# ESP32_with_USBC.net
KiCad netlist of a schematic drawn in Altium Designer
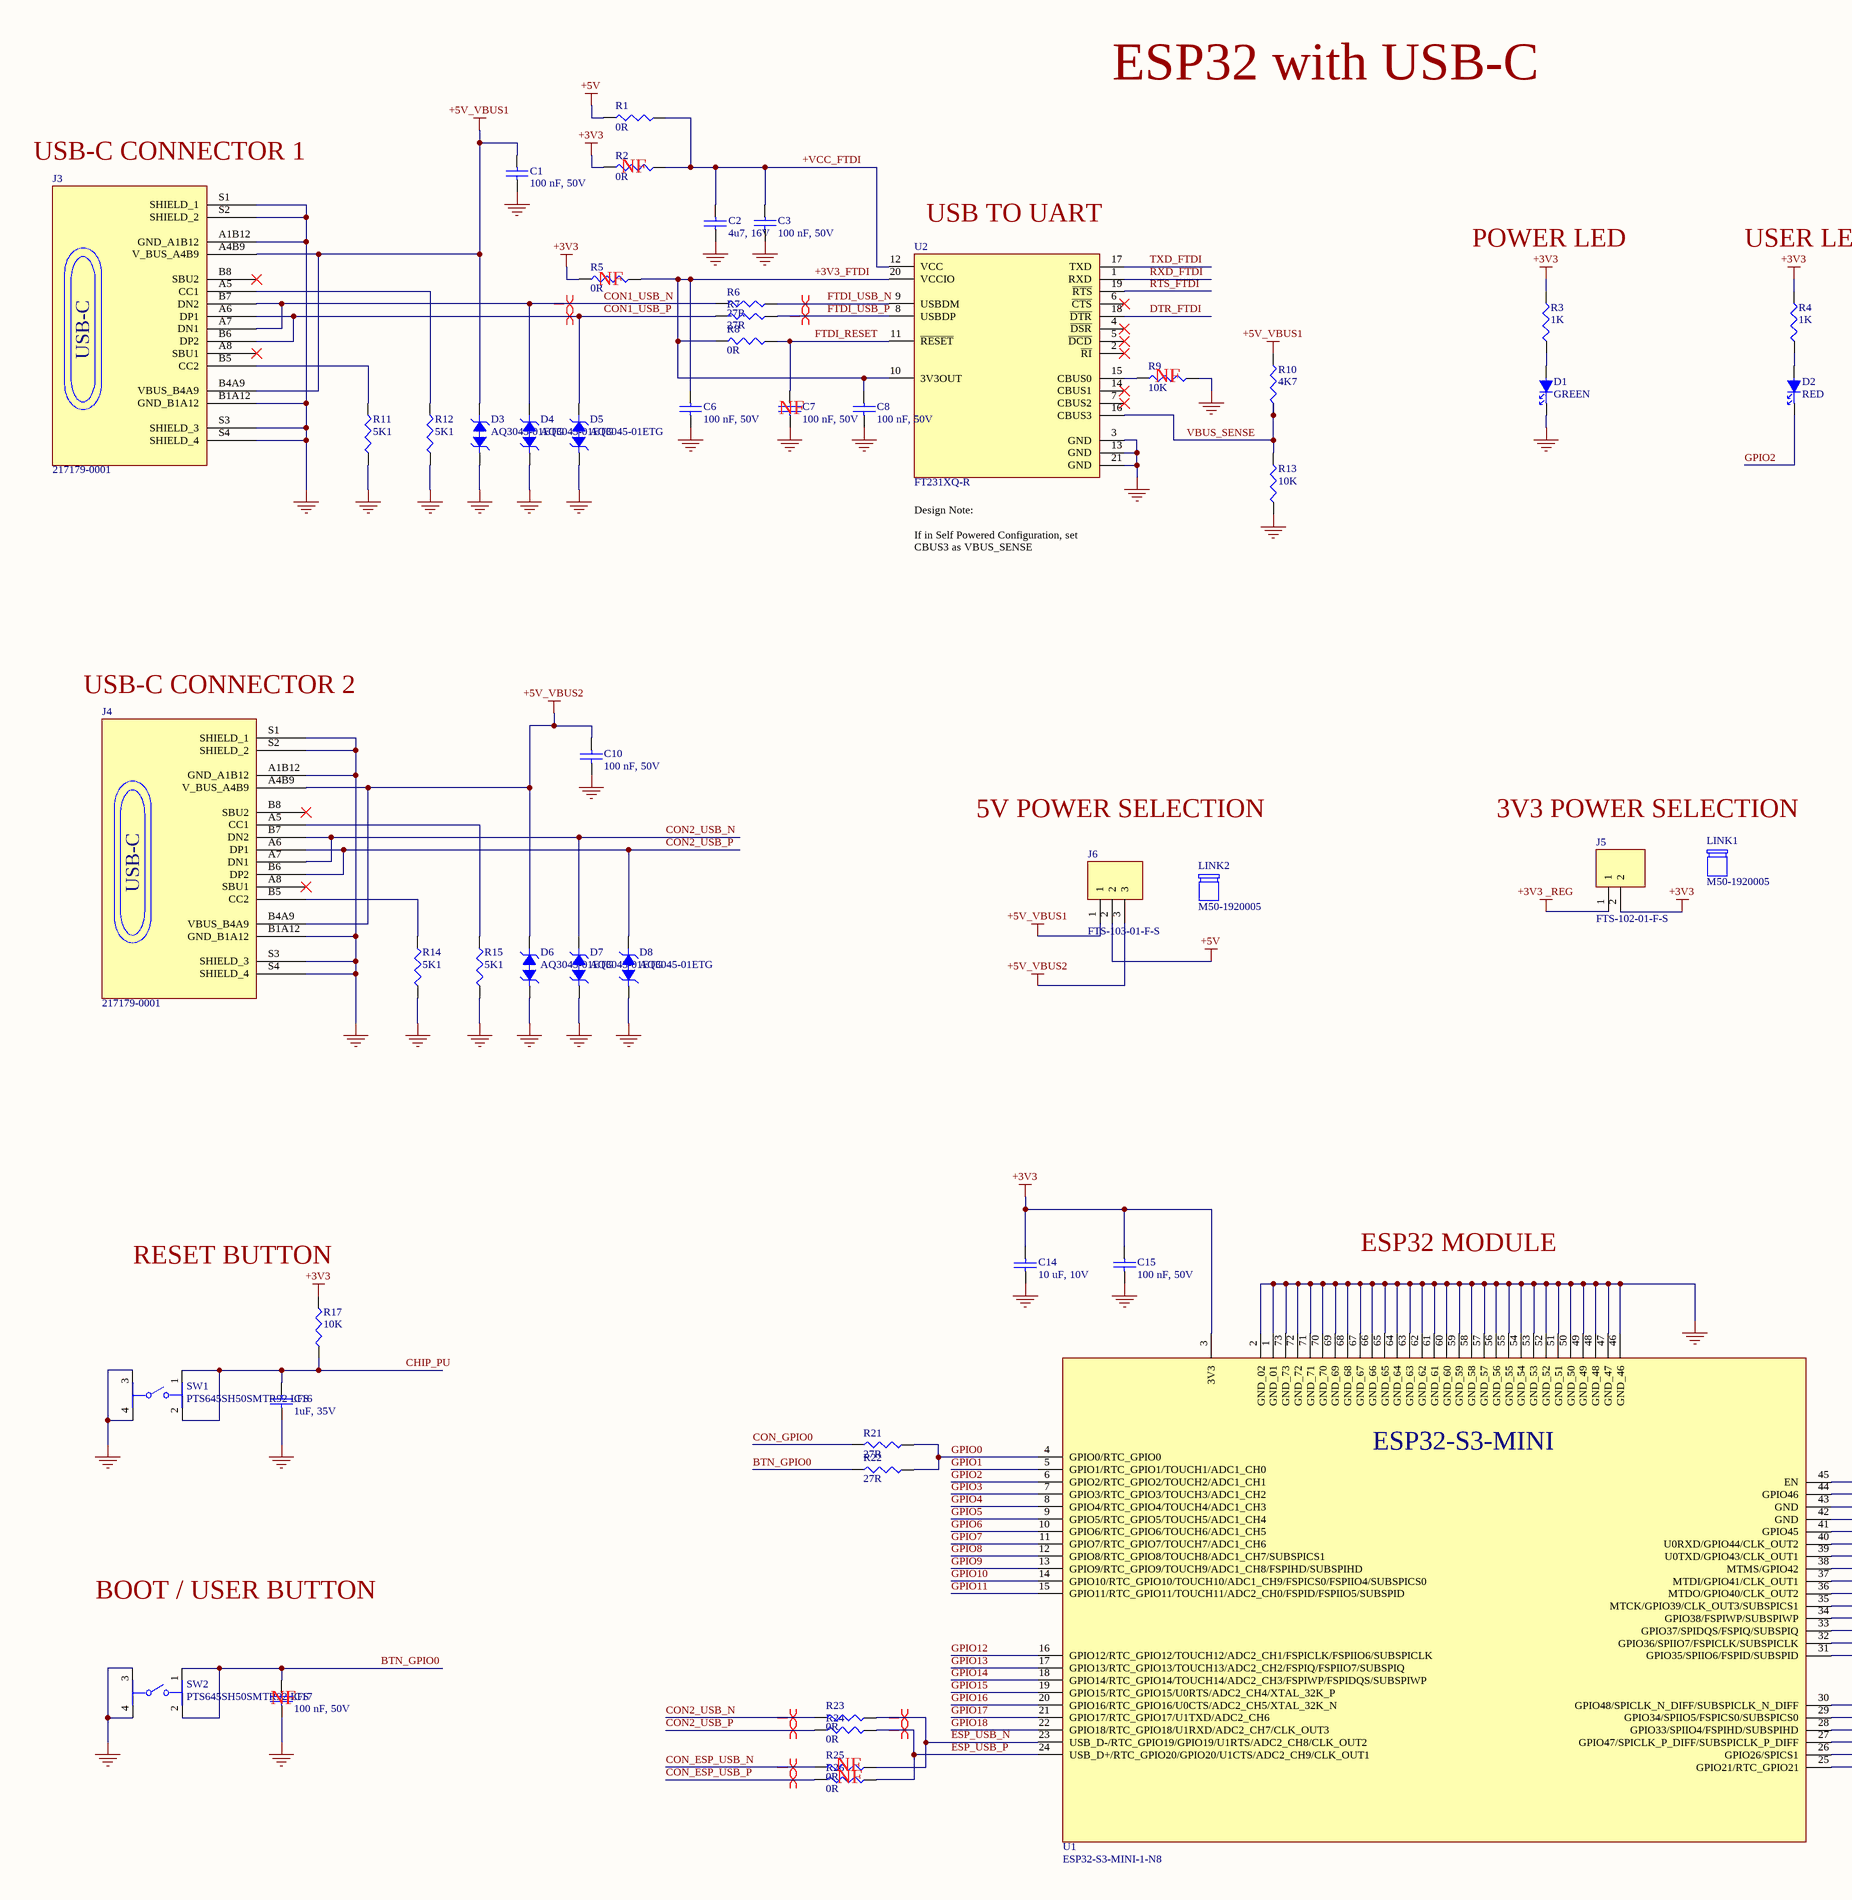
[diagram p0: ESP32 with USBC.SchDoc, left]
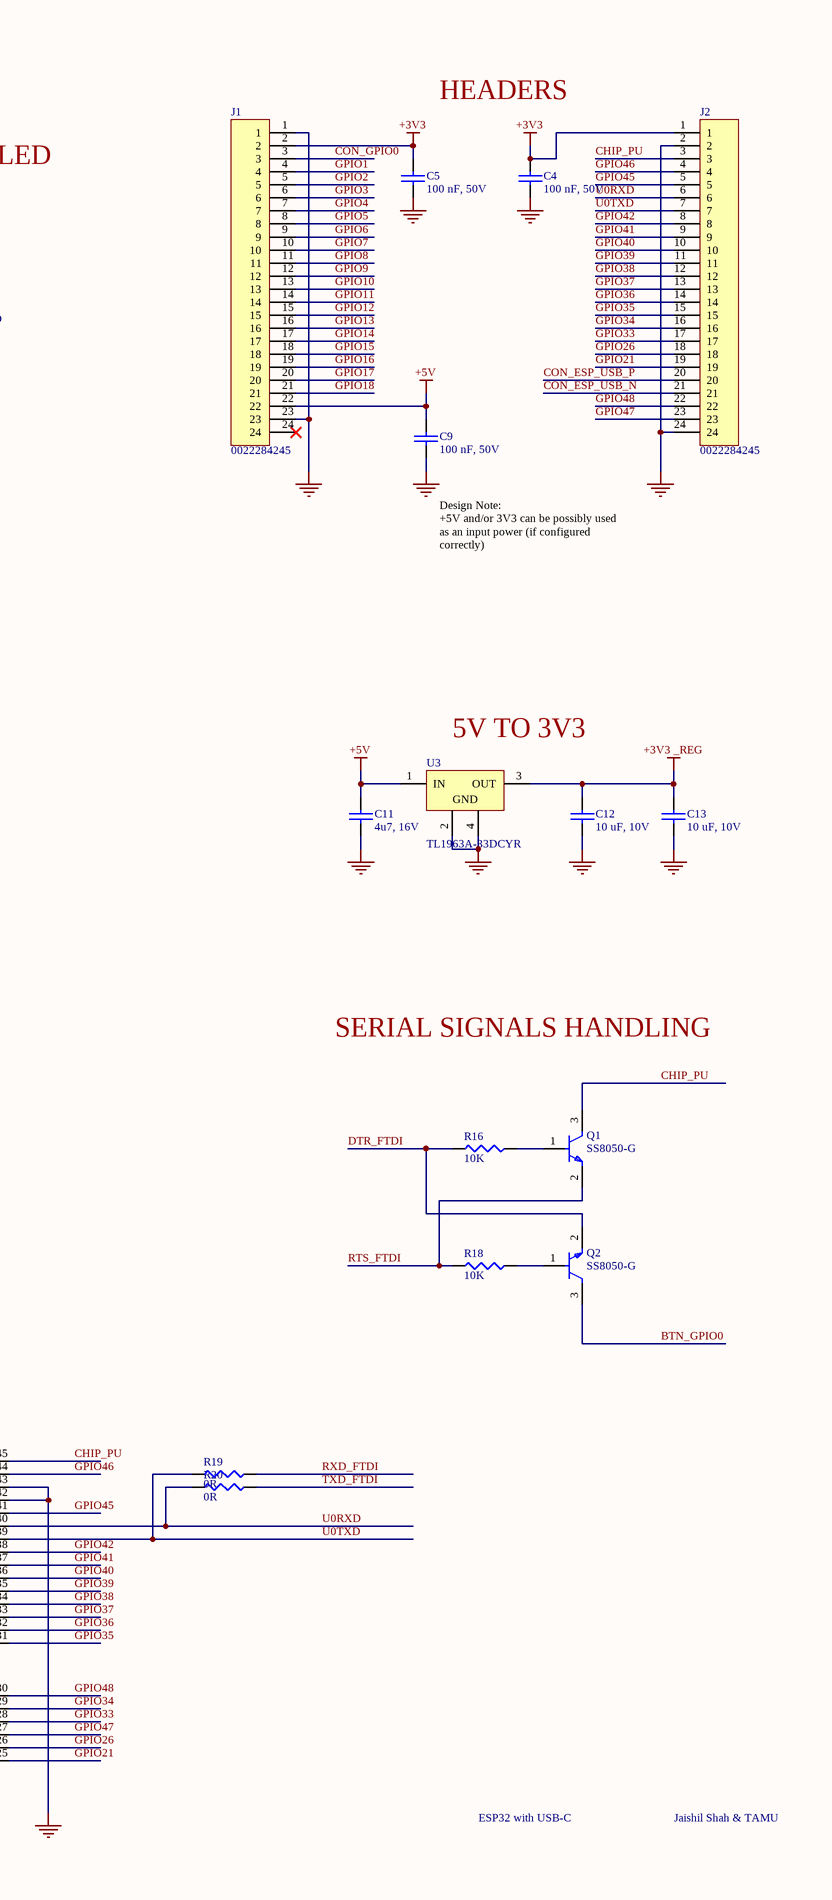
[diagram p1: ESP32 with USBC.SchDoc, right]

(export (version "E")
  (design (tool "Eeschema 10.0.6"))
  (components
    (comp (ref "C1")
      (value "100 nF, 50V")
      (footprint "CAPC1005X55N")
      (description "CAP CER 0.1UF 50V X7R 0402")
      (fields
        (field (name "MANUFACTURER") "Samsung")
        (field (name "MANUFACTURER PART NUMBER") "CL05B104KB54PNC")
      )
      (libsource (lib "Schlib") (part "CL05B104KB54PNC"))
    )
    (comp (ref "C2")
      (value "4u7, 16V")
      (footprint "CAPC1005X55N")
      (description "CAP CER 4.7UF 16V X5R 0402")
      (fields
        (field (name "MANUFACTURER") "Samsung")
        (field (name "MANUFACTURER PART NUMBER") "CL05A475MO5NUNC")
      )
      (libsource (lib "Schlib") (part "CL05A475MO5NUNC"))
    )
    (comp (ref "C3")
      (value "100 nF, 50V")
      (footprint "CAPC1005X55N")
      (description "CAP CER 0.1UF 50V X7R 0402")
      (fields
        (field (name "MANUFACTURER") "Samsung")
        (field (name "MANUFACTURER PART NUMBER") "CL05B104KB54PNC")
      )
      (libsource (lib "Schlib") (part "CL05B104KB54PNC"))
    )
    (comp (ref "C4")
      (value "100 nF, 50V")
      (footprint "CAPC1005X55N")
      (description "CAP CER 0.1UF 50V X7R 0402")
      (fields
        (field (name "MANUFACTURER") "Samsung")
        (field (name "MANUFACTURER PART NUMBER") "CL05B104KB54PNC")
      )
      (libsource (lib "Schlib") (part "CL05B104KB54PNC"))
    )
    (comp (ref "C5")
      (value "100 nF, 50V")
      (footprint "CAPC1005X55N")
      (description "CAP CER 0.1UF 50V X7R 0402")
      (fields
        (field (name "MANUFACTURER") "Samsung")
        (field (name "MANUFACTURER PART NUMBER") "CL05B104KB54PNC")
      )
      (libsource (lib "Schlib") (part "CL05B104KB54PNC"))
    )
    (comp (ref "C6")
      (value "100 nF, 50V")
      (footprint "CAPC1005X55N")
      (description "CAP CER 0.1UF 50V X7R 0402")
      (fields
        (field (name "MANUFACTURER") "Samsung")
        (field (name "MANUFACTURER PART NUMBER") "CL05B104KB54PNC")
      )
      (libsource (lib "Schlib") (part "CL05B104KB54PNC"))
    )
    (comp (ref "C7")
      (value "100 nF, 50V")
      (footprint "CAPC1005X55N")
      (description "CAP CER 0.1UF 50V X7R 0402")
      (fields
        (field (name "MANUFACTURER") "Samsung")
        (field (name "MANUFACTURER PART NUMBER") "CL05B104KB54PNC")
      )
      (libsource (lib "Schlib") (part "CL05B104KB54PNC"))
    )
    (comp (ref "C8")
      (value "100 nF, 50V")
      (footprint "CAPC1005X55N")
      (description "CAP CER 0.1UF 50V X7R 0402")
      (fields
        (field (name "MANUFACTURER") "Samsung")
        (field (name "MANUFACTURER PART NUMBER") "CL05B104KB54PNC")
      )
      (libsource (lib "Schlib") (part "CL05B104KB54PNC"))
    )
    (comp (ref "C9")
      (value "100 nF, 50V")
      (footprint "CAPC1005X55N")
      (description "CAP CER 0.1UF 50V X7R 0402")
      (fields
        (field (name "MANUFACTURER") "Samsung")
        (field (name "MANUFACTURER PART NUMBER") "CL05B104KB54PNC")
      )
      (libsource (lib "Schlib") (part "CL05B104KB54PNC"))
    )
    (comp (ref "C10")
      (value "100 nF, 50V")
      (footprint "CAPC1005X55N")
      (description "CAP CER 0.1UF 50V X7R 0402")
      (fields
        (field (name "MANUFACTURER") "Samsung")
        (field (name "MANUFACTURER PART NUMBER") "CL05B104KB54PNC")
      )
      (libsource (lib "Schlib") (part "CL05B104KB54PNC"))
    )
    (comp (ref "C11")
      (value "4u7, 16V")
      (footprint "CAPC1005X55N")
      (description "CAP CER 4.7UF 16V X5R 0402")
      (fields
        (field (name "MANUFACTURER") "Samsung")
        (field (name "MANUFACTURER PART NUMBER") "CL05A475MO5NUNC")
      )
      (libsource (lib "Schlib") (part "CL05A475MO5NUNC"))
    )
    (comp (ref "C12")
      (value "10 uF, 10V")
      (footprint "CAPC1005X55N")
      (description "CAP CER 10UF 10V X5R 0402")
      (fields
        (field (name "MANUFACTURER") "Samsung")
        (field (name "MANUFACTURER PART NUMBER") "CL05A106MP8NUB8")
      )
      (libsource (lib "Schlib") (part "CL05A106MP8NUB8"))
    )
    (comp (ref "C13")
      (value "10 uF, 10V")
      (footprint "CAPC1005X55N")
      (description "CAP CER 10UF 10V X5R 0402")
      (fields
        (field (name "MANUFACTURER") "Samsung")
        (field (name "MANUFACTURER PART NUMBER") "CL05A106MP8NUB8")
      )
      (libsource (lib "Schlib") (part "CL05A106MP8NUB8"))
    )
    (comp (ref "C14")
      (value "10 uF, 10V")
      (footprint "CAPC1005X55N")
      (description "CAP CER 10UF 10V X5R 0402")
      (fields
        (field (name "MANUFACTURER") "Samsung")
        (field (name "MANUFACTURER PART NUMBER") "CL05A106MP8NUB8")
      )
      (libsource (lib "Schlib") (part "CL05A106MP8NUB8"))
    )
    (comp (ref "C15")
      (value "100 nF, 50V")
      (footprint "CAPC1005X55N")
      (description "CAP CER 0.1UF 50V X7R 0402")
      (fields
        (field (name "MANUFACTURER") "Samsung")
        (field (name "MANUFACTURER PART NUMBER") "CL05B104KB54PNC")
      )
      (libsource (lib "Schlib") (part "CL05B104KB54PNC"))
    )
    (comp (ref "C16")
      (value "1uF, 35V")
      (footprint "CAPC1005X55N")
      (description "CAP CER 1UF 35V X5R 0402")
      (fields
        (field (name "MANUFACTURER") "Samsung")
        (field (name "MANUFACTURER PART NUMBER") "CL05A105KL5NRNC")
      )
      (libsource (lib "Schlib") (part "CL05A105KL5NRNC"))
    )
    (comp (ref "C17")
      (value "100 nF, 50V")
      (footprint "CAPC1005X55N")
      (description "CAP CER 0.1UF 50V X7R 0402")
      (fields
        (field (name "MANUFACTURER") "Samsung")
        (field (name "MANUFACTURER PART NUMBER") "CL05B104KB54PNC")
      )
      (libsource (lib "Schlib") (part "CL05B104KB54PNC"))
    )
    (comp (ref "D1")
      (value "GREEN")
      (footprint "LED0402G")
      (description "LED GREEN DIFFUSED 0402 SMD")
      (fields
        (field (name "MANUFACTURER") "Vishay")
        (field (name "MANUFACTURER PART NUMBER") "VLMTG1500-GS08")
      )
      (libsource (lib "Schlib") (part "VLMTG1500-GS08"))
    )
    (comp (ref "D2")
      (value "RED")
      (footprint "LED0402R")
      (description "LED RED 0402 SMD")
      (fields
        (field (name "MANUFACTURER") "Vishay")
        (field (name "MANUFACTURER PART NUMBER") "VLMS1500-GS08")
      )
      (libsource (lib "Schlib") (part "VLMS1500-GS08"))
    )
    (comp (ref "D3")
      (value "AQ3045-01ETG")
      (footprint "SOD882")
      (description "TVS DIODE 5.3VWM 12VC SOD882")
      (fields (field (name "MANUFACTURER") "Littelfuse"))
      (libsource (lib "Schlib") (part "AQ3045-01ETG"))
    )
    (comp (ref "D4")
      (value "AQ3045-01ETG")
      (footprint "SOD882")
      (description "TVS DIODE 5.3VWM 12VC SOD882")
      (fields (field (name "MANUFACTURER") "Littelfuse"))
      (libsource (lib "Schlib") (part "AQ3045-01ETG"))
    )
    (comp (ref "D5")
      (value "AQ3045-01ETG")
      (footprint "SOD882")
      (description "TVS DIODE 5.3VWM 12VC SOD882")
      (fields (field (name "MANUFACTURER") "Littelfuse"))
      (libsource (lib "Schlib") (part "AQ3045-01ETG"))
    )
    (comp (ref "D6")
      (value "AQ3045-01ETG")
      (footprint "SOD882")
      (description "TVS DIODE 5.3VWM 12VC SOD882")
      (fields (field (name "MANUFACTURER") "Littelfuse"))
      (libsource (lib "Schlib") (part "AQ3045-01ETG"))
    )
    (comp (ref "D7")
      (value "AQ3045-01ETG")
      (footprint "SOD882")
      (description "TVS DIODE 5.3VWM 12VC SOD882")
      (fields (field (name "MANUFACTURER") "Littelfuse"))
      (libsource (lib "Schlib") (part "AQ3045-01ETG"))
    )
    (comp (ref "D8")
      (value "AQ3045-01ETG")
      (footprint "SOD882")
      (description "TVS DIODE 5.3VWM 12VC SOD882")
      (fields (field (name "MANUFACTURER") "Littelfuse") (field (name "LCSC PART NUMBER") "C3710326"))
      (libsource (lib "Schlib") (part "AQ3045-01ETG"))
    )
    (comp (ref "J1")
      (value "0022284245")
      (footprint "HDR_1X24_2.54MM")
      (description "CONN HEADER VERT 24POS 2.54MM")
      (fields (field (name "MANUFACTURER") "Molex") (field (name "LCSC PART NUMBER") "C7145888"))
      (libsource (lib "") (part "0022284245_1"))
    )
    (comp (ref "J2")
      (value "0022284245")
      (footprint "HDR_1X24_2.54MM")
      (description "CONN HEADER VERT 24POS 2.54MM")
      (fields (field (name "MANUFACTURER") "Molex") (field (name "LCSC PART NUMBER") "C7145888"))
      (libsource (lib "Schlib") (part "0022284245"))
    )
    (comp (ref "J3")
      (value "217179-0001")
      (footprint "FP-2171790001-MFG")
      (description "CONN RCP USB2.0 TYP C 24P SMD RA")
      (fields (field (name "MANUFACTURER") "Molex") (field (name "LCSC PART NUMBER") "C3197684"))
      (libsource (lib "Schlib") (part "217179-0001"))
    )
    (comp (ref "J4")
      (value "217179-0001")
      (footprint "FP-2171790001-MFG")
      (description "CONN RCP USB2.0 TYP C 24P SMD RA")
      (fields (field (name "MANUFACTURER") "Molex") (field (name "LCSC PART NUMBER") "C3197684"))
      (libsource (lib "Schlib") (part "217179-0001"))
    )
    (comp (ref "J5")
      (value "FTS-102-01-F-S")
      (footprint "HDR_1X2_1.27MM")
      (description "CONN HEADER VERT 2POS 1.27MM")
      (fields (field (name "MANUFACTURER") "Samtec") (field (name "LCSC PART NUMBER") "C6045317"))
      (libsource (lib "Schlib") (part "FTS-102-01-F-S"))
    )
    (comp (ref "J6")
      (value "FTS-103-01-F-S")
      (footprint "HDR_1X3_1.27MM")
      (description "CONN HEADER VERT 3POS 1.27MM")
      (fields (field (name "MANUFACTURER") "Samtec") (field (name "LCSC PART NUMBER") "C3333578"))
      (libsource (lib "Schlib") (part "FTS-103-01-F-S"))
    )
    (comp (ref "LINK1")
      (value "M50-1920005")
      (description "CONN SHUNT 1.27MM RED")
      (fields (field (name "MANUFACTURER") "Harwin") (field (name "LCSC PART NUMBER") "C6985646"))
      (libsource (lib "Schlib") (part "M50-1920005"))
    )
    (comp (ref "LINK2")
      (value "M50-1920005")
      (description "CONN SHUNT 1.27MM RED")
      (fields (field (name "MANUFACTURER") "Harwin") (field (name "LCSC PART NUMBER") "C6985646"))
      (libsource (lib "Schlib") (part "M50-1920005"))
    )
    (comp (ref "Q1")
      (value "SS8050-G")
      (footprint "FP-SS8050-G-IPC_B")
      (description "TRANS NPN 25V 1.5A SOT23-3")
      (fields (field (name "MANUFACTURER") "Comchip") (field (name "LCSC PART NUMBER") "C164885"))
      (libsource (lib "Schlib") (part "SS8050-G"))
    )
    (comp (ref "Q2")
      (value "SS8050-G")
      (footprint "FP-SS8050-G-IPC_B")
      (description "TRANS NPN 25V 1.5A SOT23-3")
      (fields (field (name "MANUFACTURER") "Comchip") (field (name "LCSC PART NUMBER") "C164885"))
      (libsource (lib "Schlib") (part "SS8050-G"))
    )
    (comp (ref "R1")
      (value "0R")
      (footprint "RESC1005X37N")
      (description "RES 0 OHM JUMPER 1/16W 0402")
      (fields
        (field (name "MANUFACTURER") "Yageo")
        (field (name "MANUFACTURER PART NUMBER") "RC0402JR-070RL")
      )
      (libsource (lib "Schlib") (part "RC0402JR-070RL"))
    )
    (comp (ref "R2")
      (value "0R")
      (footprint "RESC1005X37N")
      (description "RES 0 OHM JUMPER 1/16W 0402")
      (fields
        (field (name "MANUFACTURER") "Yageo")
        (field (name "MANUFACTURER PART NUMBER") "RC0402JR-070RL")
      )
      (libsource (lib "Schlib") (part "RC0402JR-070RL"))
    )
    (comp (ref "R3")
      (value "1K")
      (footprint "RESC1005X37N")
      (description "RES 1K OHM 1% 1/16W 0402")
      (fields
        (field (name "MANUFACTURER") "Yageo")
        (field (name "MANUFACTURER PART NUMBER") "RC0402FR-071KL")
      )
      (libsource (lib "Schlib") (part "RC0402FR-071KL"))
    )
    (comp (ref "R4")
      (value "1K")
      (footprint "RESC1005X37N")
      (description "RES 1K OHM 1% 1/16W 0402")
      (fields
        (field (name "MANUFACTURER") "Yageo")
        (field (name "MANUFACTURER PART NUMBER") "RC0402FR-071KL")
      )
      (libsource (lib "Schlib") (part "RC0402FR-071KL"))
    )
    (comp (ref "R5")
      (value "0R")
      (footprint "RESC1005X37N")
      (description "RES 0 OHM JUMPER 1/16W 0402")
      (fields
        (field (name "MANUFACTURER") "Yageo")
        (field (name "MANUFACTURER PART NUMBER") "RC0402JR-070RL")
      )
      (libsource (lib "Schlib") (part "RC0402JR-070RL"))
    )
    (comp (ref "R6")
      (value "27R")
      (footprint "RESC1005X37N")
      (description "RES 27 OHM 1% 1/16W 0402")
      (fields
        (field (name "MANUFACTURER") "Yageo")
        (field (name "MANUFACTURER PART NUMBER") "RC0402FR-0727RL")
      )
      (libsource (lib "Schlib") (part "RC0402FR-0727RL"))
    )
    (comp (ref "R7")
      (value "27R")
      (footprint "RESC1005X37N")
      (description "RES 27 OHM 1% 1/16W 0402")
      (fields
        (field (name "MANUFACTURER") "Yageo")
        (field (name "MANUFACTURER PART NUMBER") "RC0402FR-0727RL")
      )
      (libsource (lib "Schlib") (part "RC0402FR-0727RL"))
    )
    (comp (ref "R8")
      (value "0R")
      (footprint "RESC1005X37N")
      (description "RES 0 OHM JUMPER 1/16W 0402")
      (fields
        (field (name "MANUFACTURER") "Yageo")
        (field (name "MANUFACTURER PART NUMBER") "RC0402JR-070RL")
      )
      (libsource (lib "Schlib") (part "RC0402JR-070RL"))
    )
    (comp (ref "R9")
      (value "10K")
      (footprint "RESC1005X37N")
      (description "RES SMD 10K OHM 1% 1/16W 0402")
      (fields
        (field (name "MANUFACTURER") "Yageo")
        (field (name "MANUFACTURER PART NUMBER") "AC0402FR-0710KL")
      )
      (libsource (lib "Schlib") (part "AC0402FR-0710KL"))
    )
    (comp (ref "R10")
      (value "4K7")
      (footprint "RESC1005X37N")
      (description "RES 4.7K OHM 1% 1/16W 0402")
      (fields
        (field (name "MANUFACTURER") "Yageo")
        (field (name "MANUFACTURER PART NUMBER") "RC0402FR-074K7L")
      )
      (libsource (lib "Schlib") (part "RC0402FR-074K7L"))
    )
    (comp (ref "R11")
      (value "5K1")
      (footprint "RESC1005X37N")
      (description "RES SMD 5.1K OHM 1% 1/16W 0402")
      (fields
        (field (name "MANUFACTURER") "Yageo")
        (field (name "MANUFACTURER PART NUMBER") "AC0402FR-075K1L")
      )
      (libsource (lib "Schlib") (part "AC0402FR-075K1L"))
    )
    (comp (ref "R12")
      (value "5K1")
      (footprint "RESC1005X37N")
      (description "RES SMD 5.1K OHM 1% 1/16W 0402")
      (fields
        (field (name "MANUFACTURER") "Yageo")
        (field (name "MANUFACTURER PART NUMBER") "AC0402FR-075K1L")
      )
      (libsource (lib "Schlib") (part "AC0402FR-075K1L"))
    )
    (comp (ref "R13")
      (value "10K")
      (footprint "RESC1005X37N")
      (description "RES SMD 10K OHM 1% 1/16W 0402")
      (fields
        (field (name "MANUFACTURER") "Yageo")
        (field (name "MANUFACTURER PART NUMBER") "AC0402FR-0710KL")
      )
      (libsource (lib "Schlib") (part "AC0402FR-0710KL"))
    )
    (comp (ref "R14")
      (value "5K1")
      (footprint "RESC1005X37N")
      (description "RES SMD 5.1K OHM 1% 1/16W 0402")
      (fields
        (field (name "MANUFACTURER") "Yageo")
        (field (name "MANUFACTURER PART NUMBER") "AC0402FR-075K1L")
      )
      (libsource (lib "Schlib") (part "AC0402FR-075K1L"))
    )
    (comp (ref "R15")
      (value "5K1")
      (footprint "RESC1005X37N")
      (description "RES SMD 5.1K OHM 1% 1/16W 0402")
      (fields
        (field (name "MANUFACTURER") "Yageo")
        (field (name "MANUFACTURER PART NUMBER") "AC0402FR-075K1L")
      )
      (libsource (lib "Schlib") (part "AC0402FR-075K1L"))
    )
    (comp (ref "R16")
      (value "10K")
      (footprint "RESC1005X37N")
      (description "RES SMD 10K OHM 1% 1/16W 0402")
      (fields
        (field (name "MANUFACTURER") "Yageo")
        (field (name "MANUFACTURER PART NUMBER") "AC0402FR-0710KL")
      )
      (libsource (lib "Schlib") (part "AC0402FR-0710KL"))
    )
    (comp (ref "R17")
      (value "10K")
      (footprint "RESC1005X37N")
      (description "RES SMD 10K OHM 1% 1/16W 0402")
      (fields
        (field (name "MANUFACTURER") "Yageo")
        (field (name "MANUFACTURER PART NUMBER") "AC0402FR-0710KL")
      )
      (libsource (lib "Schlib") (part "AC0402FR-0710KL"))
    )
    (comp (ref "R18")
      (value "10K")
      (footprint "RESC1005X37N")
      (description "RES SMD 10K OHM 1% 1/16W 0402")
      (fields
        (field (name "MANUFACTURER") "Yageo")
        (field (name "MANUFACTURER PART NUMBER") "AC0402FR-0710KL")
      )
      (libsource (lib "Schlib") (part "AC0402FR-0710KL"))
    )
    (comp (ref "R19")
      (value "0R")
      (footprint "RESC1005X37N")
      (description "RES 0 OHM JUMPER 1/16W 0402")
      (fields
        (field (name "MANUFACTURER") "Yageo")
        (field (name "MANUFACTURER PART NUMBER") "RC0402JR-070RL")
      )
      (libsource (lib "Schlib") (part "RC0402JR-070RL"))
    )
    (comp (ref "R20")
      (value "0R")
      (footprint "RESC1005X37N")
      (description "RES 0 OHM JUMPER 1/16W 0402")
      (fields
        (field (name "MANUFACTURER") "Yageo")
        (field (name "MANUFACTURER PART NUMBER") "RC0402JR-070RL")
      )
      (libsource (lib "Schlib") (part "RC0402JR-070RL"))
    )
    (comp (ref "R21")
      (value "27R")
      (footprint "RESC1005X37N")
      (description "RES 27 OHM 1% 1/16W 0402")
      (fields
        (field (name "MANUFACTURER") "Yageo")
        (field (name "MANUFACTURER PART NUMBER") "RC0402FR-0727RL")
      )
      (libsource (lib "Schlib") (part "RC0402FR-0727RL"))
    )
    (comp (ref "R22")
      (value "27R")
      (footprint "RESC1005X37N")
      (description "RES 27 OHM 1% 1/16W 0402")
      (fields
        (field (name "MANUFACTURER") "Yageo")
        (field (name "MANUFACTURER PART NUMBER") "RC0402FR-0727RL")
      )
      (libsource (lib "Schlib") (part "RC0402FR-0727RL"))
    )
    (comp (ref "R23")
      (value "0R")
      (footprint "RESC1005X37N")
      (description "RES 0 OHM JUMPER 1/16W 0402")
      (fields
        (field (name "MANUFACTURER") "Yageo")
        (field (name "MANUFACTURER PART NUMBER") "RC0402JR-070RL")
      )
      (libsource (lib "Schlib") (part "RC0402JR-070RL"))
    )
    (comp (ref "R24")
      (value "0R")
      (footprint "RESC1005X37N")
      (description "RES 0 OHM JUMPER 1/16W 0402")
      (fields
        (field (name "MANUFACTURER") "Yageo")
        (field (name "MANUFACTURER PART NUMBER") "RC0402JR-070RL")
      )
      (libsource (lib "Schlib") (part "RC0402JR-070RL"))
    )
    (comp (ref "R25")
      (value "0R")
      (footprint "RESC1005X37N")
      (description "RES 0 OHM JUMPER 1/16W 0402")
      (fields
        (field (name "MANUFACTURER") "Yageo")
        (field (name "MANUFACTURER PART NUMBER") "RC0402JR-070RL")
      )
      (libsource (lib "Schlib") (part "RC0402JR-070RL"))
    )
    (comp (ref "R26")
      (value "0R")
      (footprint "RESC1005X37N")
      (description "RES 0 OHM JUMPER 1/16W 0402")
      (fields
        (field (name "MANUFACTURER") "Yageo")
        (field (name "MANUFACTURER PART NUMBER") "RC0402JR-070RL")
      )
      (libsource (lib "Schlib") (part "RC0402JR-070RL"))
    )
    (comp (ref "SW1")
      (value "PTS645SH50SMTR92 LFS")
      (footprint "FP-PTS645SH50SMTR92LFS-MFG")
      (description "SWITCH TACTILE SPST-NO 0.05A 12V")
      (fields
        (field (name "MANUFACTURER") "ITT C&K")
        (field (name "MANUFACTURER PART NUMBER") "PTS645SH50SMTR92LFS")
      )
      (libsource (lib "Schlib") (part "PTS645SH50SMTR92LFS"))
    )
    (comp (ref "SW2")
      (value "PTS645SH50SMTR92 LFS")
      (footprint "FP-PTS645SH50SMTR92LFS-MFG")
      (description "SWITCH TACTILE SPST-NO 0.05A 12V")
      (fields
        (field (name "MANUFACTURER") "ITT C&K")
        (field (name "MANUFACTURER PART NUMBER") "PTS645SH50SMTR92LFS")
      )
      (libsource (lib "Schlib") (part "PTS645SH50SMTR92LFS"))
    )
    (comp (ref "U1")
      (value "ESP32-S3-MINI-1-N8")
      (footprint "XCVR_ESP32-S3-MINI-1-N8")
      (description "SMD module, ESP32-S3FN8, 8 MB SPI flash, PCB antenna")
      (fields (field (name "MANUFACTURER") "Espressif Systems") (field (name "LCSC PART NUMBER") "C2913206"))
      (libsource (lib "Schlib") (part "ESP32-S3-MINI-1-N8"))
    )
    (comp (ref "U2")
      (value "FT231XQ-R")
      (footprint "FP-QFN-20-IPC_B")
      (description "IC USB SERIAL FULL UART 20QFN")
      (fields (field (name "MANUFACTURER") "FTDI") (field (name "LCSC PART NUMBER") "C132159"))
      (libsource (lib "Schlib") (part "FT231XQ-R"))
    )
    (comp (ref "U3")
      (value "TL1963A-33DCYR")
      (footprint "DCY0004A_N")
      (description "IC REG LINEAR 3.3V 1.5A SOT223-4")
      (fields (field (name "MANUFACTURER") "Texas Instruments") (field (name "LCSC PART NUMBER") "C181262"))
      (libsource (lib "Schlib") (part "TL1963A-33DCYR"))
    )
  )
  (nets
    (net (code "1") (name "+3V3") (class "Default")
      (node (ref "C14") (pin "2") (pinfunction "2_2") (pintype "passive"))
      (node (ref "C15") (pin "1") (pinfunction "1_1") (pintype "passive"))
      (node (ref "C4") (pin "1") (pinfunction "1_1") (pintype "passive"))
      (node (ref "C5") (pin "1") (pinfunction "1_1") (pintype "passive"))
      (node (ref "J1") (pin "2") (pinfunction "2_2") (pintype "passive"))
      (node (ref "J2") (pin "1") (pinfunction "1_1") (pintype "passive"))
      (node (ref "J5") (pin "2") (pinfunction "2_2") (pintype "passive"))
      (node (ref "R17") (pin "1") (pinfunction "1_1") (pintype "passive"))
      (node (ref "R2") (pin "1") (pinfunction "1_1") (pintype "passive"))
      (node (ref "R3") (pin "2") (pinfunction "2_2") (pintype "passive"))
      (node (ref "R4") (pin "2") (pinfunction "2_2") (pintype "passive"))
      (node (ref "R5") (pin "1") (pinfunction "1_1") (pintype "passive"))
      (node (ref "U1") (pin "3") (pinfunction "3V3_3") (pintype "passive"))
    )
    (net (code "2") (name "+3V3 _REG") (class "Default")
      (node (ref "C12") (pin "2") (pinfunction "2_2") (pintype "passive"))
      (node (ref "C13") (pin "2") (pinfunction "2_2") (pintype "passive"))
      (node (ref "J5") (pin "1") (pinfunction "1_1") (pintype "passive"))
      (node (ref "U3") (pin "3") (pinfunction "OUT_3") (pintype "power_in"))
    )
    (net (code "3") (name "+5V") (class "Default")
      (node (ref "C11") (pin "2") (pinfunction "2_2") (pintype "passive"))
      (node (ref "C9") (pin "1") (pinfunction "1_1") (pintype "passive"))
      (node (ref "J1") (pin "22") (pinfunction "22_22") (pintype "passive"))
      (node (ref "J6") (pin "2") (pinfunction "2_2") (pintype "passive"))
      (node (ref "R1") (pin "1") (pinfunction "1_1") (pintype "passive"))
      (node (ref "U3") (pin "1") (pinfunction "IN_1") (pintype "power_in"))
    )
    (net (code "4") (name "+5V_VBUS1") (class "Default")
      (node (ref "C1") (pin "1") (pinfunction "1_1") (pintype "passive"))
      (node (ref "D3") (pin "2") (pinfunction "2_2") (pintype "passive"))
      (node (ref "J3") (pin "A4B9") (pinfunction "V_BUS_A4B9_A4B9") (pintype "passive"))
      (node (ref "J3") (pin "B4A9") (pinfunction "VBUS_B4A9_B4A9") (pintype "passive"))
      (node (ref "J6") (pin "1") (pinfunction "1_1") (pintype "passive"))
      (node (ref "R10") (pin "2") (pinfunction "2_2") (pintype "passive"))
    )
    (net (code "5") (name "+5V_VBUS2") (class "Default")
      (node (ref "C10") (pin "1") (pinfunction "1_1") (pintype "passive"))
      (node (ref "D6") (pin "2") (pinfunction "2_2") (pintype "passive"))
      (node (ref "J4") (pin "A4B9") (pinfunction "V_BUS_A4B9_A4B9") (pintype "passive"))
      (node (ref "J4") (pin "B4A9") (pinfunction "VBUS_B4A9_B4A9") (pintype "passive"))
      (node (ref "J6") (pin "3") (pinfunction "3_3") (pintype "passive"))
    )
    (net (code "6") (name "/+3V3_FTDI") (class "Default")
      (node (ref "C6") (pin "1") (pinfunction "1_1") (pintype "passive"))
      (node (ref "C8") (pin "1") (pinfunction "1_1") (pintype "passive"))
      (node (ref "R5") (pin "2") (pinfunction "2_2") (pintype "passive"))
      (node (ref "R8") (pin "1") (pinfunction "1_1") (pintype "passive"))
      (node (ref "U2") (pin "10") (pinfunction "3V3OUT_10") (pintype "passive"))
      (node (ref "U2") (pin "20") (pinfunction "VCCIO_20") (pintype "passive"))
    )
    (net (code "7") (name "/+VCC_FTDI") (class "Default")
      (node (ref "C2") (pin "2") (pinfunction "2_2") (pintype "passive"))
      (node (ref "C3") (pin "1") (pinfunction "1_1") (pintype "passive"))
      (node (ref "R1") (pin "2") (pinfunction "2_2") (pintype "passive"))
      (node (ref "R2") (pin "2") (pinfunction "2_2") (pintype "passive"))
      (node (ref "U2") (pin "12") (pinfunction "VCC_12") (pintype "passive"))
    )
    (net (code "8") (name "/BTN_GPIO0") (class "Default")
      (node (ref "C17") (pin "1") (pinfunction "1_1") (pintype "passive"))
      (node (ref "Q2") (pin "3") (pinfunction "C_3") (pintype "passive"))
      (node (ref "R22") (pin "1") (pinfunction "1_1") (pintype "passive"))
      (node (ref "SW2") (pin "1") (pinfunction "1_1") (pintype "passive"))
      (node (ref "SW2") (pin "2") (pinfunction "2_2") (pintype "passive"))
    )
    (net (code "9") (name "/CHIP_PU") (class "Default")
      (node (ref "C16") (pin "2") (pinfunction "2_2") (pintype "passive"))
      (node (ref "J2") (pin "3") (pinfunction "3_3") (pintype "passive"))
      (node (ref "Q1") (pin "3") (pinfunction "C_3") (pintype "passive"))
      (node (ref "R17") (pin "2") (pinfunction "2_2") (pintype "passive"))
      (node (ref "SW1") (pin "1") (pinfunction "1_1") (pintype "passive"))
      (node (ref "SW1") (pin "2") (pinfunction "2_2") (pintype "passive"))
      (node (ref "U1") (pin "45") (pinfunction "EN_45") (pintype "passive"))
    )
    (net (code "10") (name "/CON1_USB_N") (class "Default")
      (node (ref "D4") (pin "2") (pinfunction "2_2") (pintype "passive"))
      (node (ref "J3") (pin "A7") (pinfunction "DN1_A7") (pintype "passive"))
      (node (ref "J3") (pin "B7") (pinfunction "DN2_B7") (pintype "passive"))
      (node (ref "R6") (pin "1") (pinfunction "1_1") (pintype "passive"))
    )
    (net (code "11") (name "/CON1_USB_P") (class "Default")
      (node (ref "D5") (pin "2") (pinfunction "2_2") (pintype "passive"))
      (node (ref "J3") (pin "A6") (pinfunction "DP1_A6") (pintype "passive"))
      (node (ref "J3") (pin "B6") (pinfunction "DP2_B6") (pintype "passive"))
      (node (ref "R7") (pin "1") (pinfunction "1_1") (pintype "passive"))
    )
    (net (code "12") (name "/CON2_USB_N") (class "Default")
      (node (ref "D7") (pin "2") (pinfunction "2_2") (pintype "passive"))
      (node (ref "J4") (pin "A7") (pinfunction "DN1_A7") (pintype "passive"))
      (node (ref "J4") (pin "B7") (pinfunction "DN2_B7") (pintype "passive"))
      (node (ref "R23") (pin "1") (pinfunction "1_1") (pintype "passive"))
    )
    (net (code "13") (name "/CON2_USB_P") (class "Default")
      (node (ref "D8") (pin "2") (pinfunction "2_2") (pintype "passive"))
      (node (ref "J4") (pin "A6") (pinfunction "DP1_A6") (pintype "passive"))
      (node (ref "J4") (pin "B6") (pinfunction "DP2_B6") (pintype "passive"))
      (node (ref "R24") (pin "1") (pinfunction "1_1") (pintype "passive"))
    )
    (net (code "14") (name "/CON_ESP_USB_N") (class "Default")
      (node (ref "J2") (pin "21") (pinfunction "21_21") (pintype "passive"))
      (node (ref "R25") (pin "1") (pinfunction "1_1") (pintype "passive"))
    )
    (net (code "15") (name "/CON_ESP_USB_P") (class "Default")
      (node (ref "J2") (pin "20") (pinfunction "20_20") (pintype "passive"))
      (node (ref "R26") (pin "1") (pinfunction "1_1") (pintype "passive"))
    )
    (net (code "16") (name "/CON_GPIO0") (class "Default")
      (node (ref "J1") (pin "3") (pinfunction "3_3") (pintype "passive"))
      (node (ref "R21") (pin "1") (pinfunction "1_1") (pintype "passive"))
    )
    (net (code "17") (name "/DTR_FTDI") (class "Default")
      (node (ref "Q2") (pin "2") (pinfunction "E_2") (pintype "passive"))
      (node (ref "R16") (pin "2") (pinfunction "2_2") (pintype "passive"))
      (node (ref "U2") (pin "18") (pinfunction "~{DTR}_18") (pintype "passive"))
    )
    (net (code "18") (name "/ESP_USB_N") (class "Default")
      (node (ref "R23") (pin "2") (pinfunction "2_2") (pintype "passive"))
      (node (ref "R25") (pin "2") (pinfunction "2_2") (pintype "passive"))
      (node (ref "U1") (pin "23") (pinfunction "USB_D-/RTC_GPIO19/GPIO19/U1RTS/ADC2_CH8/CLK_OUT2_23") (pintype "passive"))
    )
    (net (code "19") (name "/ESP_USB_P") (class "Default")
      (node (ref "R24") (pin "2") (pinfunction "2_2") (pintype "passive"))
      (node (ref "R26") (pin "2") (pinfunction "2_2") (pintype "passive"))
      (node (ref "U1") (pin "24") (pinfunction "USB_D+/RTC_GPIO20/GPIO20/U1CTS/ADC2_CH9/CLK_OUT1_24") (pintype "passive"))
    )
    (net (code "20") (name "/FTDI_RESET") (class "Default")
      (node (ref "C7") (pin "1") (pinfunction "1_1") (pintype "passive"))
      (node (ref "R8") (pin "2") (pinfunction "2_2") (pintype "passive"))
      (node (ref "U2") (pin "11") (pinfunction "~{RESET}_11") (pintype "passive"))
    )
    (net (code "21") (name "/FTDI_USB_N") (class "Default")
      (node (ref "R6") (pin "2") (pinfunction "2_2") (pintype "passive"))
      (node (ref "U2") (pin "9") (pinfunction "USBDM_9") (pintype "passive"))
    )
    (net (code "22") (name "/FTDI_USB_P") (class "Default")
      (node (ref "R7") (pin "2") (pinfunction "2_2") (pintype "passive"))
      (node (ref "U2") (pin "8") (pinfunction "USBDP_8") (pintype "passive"))
    )
    (net (code "23") (name "/GPIO0") (class "Default")
      (node (ref "R21") (pin "2") (pinfunction "2_2") (pintype "passive"))
      (node (ref "R22") (pin "2") (pinfunction "2_2") (pintype "passive"))
      (node (ref "U1") (pin "4") (pinfunction "GPIO0/RTC_GPIO0_4") (pintype "passive"))
    )
    (net (code "24") (name "/GPIO1") (class "Default")
      (node (ref "J1") (pin "4") (pinfunction "4_4") (pintype "passive"))
      (node (ref "U1") (pin "5") (pinfunction "GPIO1/RTC_GPIO1/TOUCH1/ADC1_CH0_5") (pintype "passive"))
    )
    (net (code "25") (name "/GPIO2") (class "Default")
      (node (ref "D2") (pin "1") (pinfunction "1_1") (pintype "passive"))
      (node (ref "J1") (pin "5") (pinfunction "5_5") (pintype "passive"))
      (node (ref "U1") (pin "6") (pinfunction "GPIO2/RTC_GPIO2/TOUCH2/ADC1_CH1_6") (pintype "passive"))
    )
    (net (code "26") (name "/GPIO3") (class "Default")
      (node (ref "J1") (pin "6") (pinfunction "6_6") (pintype "passive"))
      (node (ref "U1") (pin "7") (pinfunction "GPIO3/RTC_GPIO3/TOUCH3/ADC1_CH2_7") (pintype "passive"))
    )
    (net (code "27") (name "/GPIO4") (class "Default")
      (node (ref "J1") (pin "7") (pinfunction "7_7") (pintype "passive"))
      (node (ref "U1") (pin "8") (pinfunction "GPIO4/RTC_GPIO4/TOUCH4/ADC1_CH3_8") (pintype "passive"))
    )
    (net (code "28") (name "/GPIO5") (class "Default")
      (node (ref "J1") (pin "8") (pinfunction "8_8") (pintype "passive"))
      (node (ref "U1") (pin "9") (pinfunction "GPIO5/RTC_GPIO5/TOUCH5/ADC1_CH4_9") (pintype "passive"))
    )
    (net (code "29") (name "/GPIO6") (class "Default")
      (node (ref "J1") (pin "9") (pinfunction "9_9") (pintype "passive"))
      (node (ref "U1") (pin "10") (pinfunction "GPIO6/RTC_GPIO6/TOUCH6/ADC1_CH5_10") (pintype "passive"))
    )
    (net (code "30") (name "/GPIO7") (class "Default")
      (node (ref "J1") (pin "10") (pinfunction "10_10") (pintype "passive"))
      (node (ref "U1") (pin "11") (pinfunction "GPIO7/RTC_GPIO7/TOUCH7/ADC1_CH6_11") (pintype "passive"))
    )
    (net (code "31") (name "/GPIO8") (class "Default")
      (node (ref "J1") (pin "11") (pinfunction "11_11") (pintype "passive"))
      (node (ref "U1") (pin "12") (pinfunction "GPIO8/RTC_GPIO8/TOUCH8/ADC1_CH7/SUBSPICS1_12") (pintype "passive"))
    )
    (net (code "32") (name "/GPIO9") (class "Default")
      (node (ref "J1") (pin "12") (pinfunction "12_12") (pintype "passive"))
      (node (ref "U1") (pin "13") (pinfunction "GPIO9/RTC_GPIO9/TOUCH9/ADC1_CH8/FSPIHD/SUBSPIHD_13") (pintype "passive"))
    )
    (net (code "33") (name "/GPIO10") (class "Default")
      (node (ref "J1") (pin "13") (pinfunction "13_13") (pintype "passive"))
      (node (ref "U1") (pin "14") (pinfunction "GPIO10/RTC_GPIO10/TOUCH10/ADC1_CH9/FSPICS0/FSPIIO4/SUBSPICS0_14") (pintype "passive"))
    )
    (net (code "34") (name "/GPIO11") (class "Default")
      (node (ref "J1") (pin "14") (pinfunction "14_14") (pintype "passive"))
      (node (ref "U1") (pin "15") (pinfunction "GPIO11/RTC_GPIO11/TOUCH11/ADC2_CH0/FSPID/FSPIIO5/SUBSPID_15") (pintype "passive"))
    )
    (net (code "35") (name "/GPIO12") (class "Default")
      (node (ref "J1") (pin "15") (pinfunction "15_15") (pintype "passive"))
      (node (ref "U1") (pin "16") (pinfunction "GPIO12/RTC_GPIO12/TOUCH12/ADC2_CH1/FSPICLK/FSPIIO6/SUBSPICLK_16") (pintype "passive"))
    )
    (net (code "36") (name "/GPIO13") (class "Default")
      (node (ref "J1") (pin "16") (pinfunction "16_16") (pintype "passive"))
      (node (ref "U1") (pin "17") (pinfunction "GPIO13/RTC_GPIO13/TOUCH13/ADC2_CH2/FSPIQ/FSPIIO7/SUBSPIQ_17") (pintype "passive"))
    )
    (net (code "37") (name "/GPIO14") (class "Default")
      (node (ref "J1") (pin "17") (pinfunction "17_17") (pintype "passive"))
      (node (ref "U1") (pin "18") (pinfunction "GPIO14/RTC_GPIO14/TOUCH14/ADC2_CH3/FSPIWP/FSPIDQS/SUBSPIWP_18") (pintype "passive"))
    )
    (net (code "38") (name "/GPIO15") (class "Default")
      (node (ref "J1") (pin "18") (pinfunction "18_18") (pintype "passive"))
      (node (ref "U1") (pin "19") (pinfunction "GPIO15/RTC_GPIO15/U0RTS/ADC2_CH4/XTAL_32K_P_19") (pintype "passive"))
    )
    (net (code "39") (name "/GPIO16") (class "Default")
      (node (ref "J1") (pin "19") (pinfunction "19_19") (pintype "passive"))
      (node (ref "U1") (pin "20") (pinfunction "GPIO16/RTC_GPIO16/U0CTS/ADC2_CH5/XTAL_32K_N_20") (pintype "passive"))
    )
    (net (code "40") (name "/GPIO17") (class "Default")
      (node (ref "J1") (pin "20") (pinfunction "20_20") (pintype "passive"))
      (node (ref "U1") (pin "21") (pinfunction "GPIO17/RTC_GPIO17/U1TXD/ADC2_CH6_21") (pintype "passive"))
    )
    (net (code "41") (name "/GPIO18") (class "Default")
      (node (ref "J1") (pin "21") (pinfunction "21_21") (pintype "passive"))
      (node (ref "U1") (pin "22") (pinfunction "GPIO18/RTC_GPIO18/U1RXD/ADC2_CH7/CLK_OUT3_22") (pintype "passive"))
    )
    (net (code "42") (name "/GPIO21") (class "Default")
      (node (ref "J2") (pin "19") (pinfunction "19_19") (pintype "passive"))
      (node (ref "U1") (pin "25") (pinfunction "GPIO21/RTC_GPIO21_25") (pintype "passive"))
    )
    (net (code "43") (name "/GPIO26") (class "Default")
      (node (ref "J2") (pin "18") (pinfunction "18_18") (pintype "passive"))
      (node (ref "U1") (pin "26") (pinfunction "GPIO26/SPICS1_26") (pintype "passive"))
    )
    (net (code "44") (name "/GPIO33") (class "Default")
      (node (ref "J2") (pin "17") (pinfunction "17_17") (pintype "passive"))
      (node (ref "U1") (pin "28") (pinfunction "GPIO33/SPIIO4/FSPIHD/SUBSPIHD_28") (pintype "passive"))
    )
    (net (code "45") (name "/GPIO34") (class "Default")
      (node (ref "J2") (pin "16") (pinfunction "16_16") (pintype "passive"))
      (node (ref "U1") (pin "29") (pinfunction "GPIO34/SPIIO5/FSPICS0/SUBSPICS0_29") (pintype "passive"))
    )
    (net (code "46") (name "/GPIO35") (class "Default")
      (node (ref "J2") (pin "15") (pinfunction "15_15") (pintype "passive"))
      (node (ref "U1") (pin "31") (pinfunction "GPIO35/SPIIO6/FSPID/SUBSPID_31") (pintype "passive"))
    )
    (net (code "47") (name "/GPIO36") (class "Default")
      (node (ref "J2") (pin "14") (pinfunction "14_14") (pintype "passive"))
      (node (ref "U1") (pin "32") (pinfunction "GPIO36/SPIIO7/FSPICLK/SUBSPICLK_32") (pintype "passive"))
    )
    (net (code "48") (name "/GPIO37") (class "Default")
      (node (ref "J2") (pin "13") (pinfunction "13_13") (pintype "passive"))
      (node (ref "U1") (pin "33") (pinfunction "GPIO37/SPIDQS/FSPIQ/SUBSPIQ_33") (pintype "passive"))
    )
    (net (code "49") (name "/GPIO38") (class "Default")
      (node (ref "J2") (pin "12") (pinfunction "12_12") (pintype "passive"))
      (node (ref "U1") (pin "34") (pinfunction "GPIO38/FSPIWP/SUBSPIWP_34") (pintype "passive"))
    )
    (net (code "50") (name "/GPIO39") (class "Default")
      (node (ref "J2") (pin "11") (pinfunction "11_11") (pintype "passive"))
      (node (ref "U1") (pin "35") (pinfunction "MTCK/GPIO39/CLK_OUT3/SUBSPICS1_35") (pintype "passive"))
    )
    (net (code "51") (name "/GPIO40") (class "Default")
      (node (ref "J2") (pin "10") (pinfunction "10_10") (pintype "passive"))
      (node (ref "U1") (pin "36") (pinfunction "MTDO/GPIO40/CLK_OUT2_36") (pintype "passive"))
    )
    (net (code "52") (name "/GPIO41") (class "Default")
      (node (ref "J2") (pin "9") (pinfunction "9_9") (pintype "passive"))
      (node (ref "U1") (pin "37") (pinfunction "MTDI/GPIO41/CLK_OUT1_37") (pintype "passive"))
    )
    (net (code "53") (name "/GPIO42") (class "Default")
      (node (ref "J2") (pin "8") (pinfunction "8_8") (pintype "passive"))
      (node (ref "U1") (pin "38") (pinfunction "MTMS/GPIO42_38") (pintype "passive"))
    )
    (net (code "54") (name "/GPIO45") (class "Default")
      (node (ref "J2") (pin "5") (pinfunction "5_5") (pintype "passive"))
      (node (ref "U1") (pin "41") (pinfunction "GPIO45_41") (pintype "passive"))
    )
    (net (code "55") (name "/GPIO46") (class "Default")
      (node (ref "J2") (pin "4") (pinfunction "4_4") (pintype "passive"))
      (node (ref "U1") (pin "44") (pinfunction "GPIO46_44") (pintype "passive"))
    )
    (net (code "56") (name "/GPIO47") (class "Default")
      (node (ref "J2") (pin "23") (pinfunction "23_23") (pintype "passive"))
      (node (ref "U1") (pin "27") (pinfunction "GPIO47/SPICLK_P_DIFF/SUBSPICLK_P_DIFF_27") (pintype "passive"))
    )
    (net (code "57") (name "/GPIO48") (class "Default")
      (node (ref "J2") (pin "22") (pinfunction "22_22") (pintype "passive"))
      (node (ref "U1") (pin "30") (pinfunction "GPIO48/SPICLK_N_DIFF/SUBSPICLK_N_DIFF_30") (pintype "passive"))
    )
    (net (code "58") (name "/RTS_FTDI") (class "Default")
      (node (ref "Q1") (pin "2") (pinfunction "E_2") (pintype "passive"))
      (node (ref "R18") (pin "2") (pinfunction "2_2") (pintype "passive"))
      (node (ref "U2") (pin "19") (pinfunction "~{RTS}_19") (pintype "passive"))
    )
    (net (code "59") (name "/RXD_FTDI") (class "Default")
      (node (ref "R19") (pin "2") (pinfunction "2_2") (pintype "passive"))
      (node (ref "U2") (pin "1") (pinfunction "RXD_1") (pintype "passive"))
    )
    (net (code "60") (name "/TXD_FTDI") (class "Default")
      (node (ref "R20") (pin "2") (pinfunction "2_2") (pintype "passive"))
      (node (ref "U2") (pin "17") (pinfunction "TXD_17") (pintype "passive"))
    )
    (net (code "61") (name "/U0RXD") (class "Default")
      (node (ref "J2") (pin "6") (pinfunction "6_6") (pintype "passive"))
      (node (ref "R20") (pin "1") (pinfunction "1_1") (pintype "passive"))
      (node (ref "U1") (pin "40") (pinfunction "U0RXD/GPIO44/CLK_OUT2_40") (pintype "passive"))
    )
    (net (code "62") (name "/U0TXD") (class "Default")
      (node (ref "J2") (pin "7") (pinfunction "7_7") (pintype "passive"))
      (node (ref "R19") (pin "1") (pinfunction "1_1") (pintype "passive"))
      (node (ref "U1") (pin "39") (pinfunction "U0TXD/GPIO43/CLK_OUT1_39") (pintype "passive"))
    )
    (net (code "63") (name "/VBUS_SENSE") (class "Default")
      (node (ref "R10") (pin "1") (pinfunction "1_1") (pintype "passive"))
      (node (ref "R13") (pin "2") (pinfunction "2_2") (pintype "passive"))
      (node (ref "U2") (pin "16") (pinfunction "CBUS3_16") (pintype "passive"))
    )
    (net (code "64") (name "GND") (class "Default")
      (node (ref "C1") (pin "2") (pinfunction "2_2") (pintype "passive"))
      (node (ref "C10") (pin "2") (pinfunction "2_2") (pintype "passive"))
      (node (ref "C11") (pin "1") (pinfunction "1_1") (pintype "passive"))
      (node (ref "C12") (pin "1") (pinfunction "1_1") (pintype "passive"))
      (node (ref "C13") (pin "1") (pinfunction "1_1") (pintype "passive"))
      (node (ref "C14") (pin "1") (pinfunction "1_1") (pintype "passive"))
      (node (ref "C15") (pin "2") (pinfunction "2_2") (pintype "passive"))
      (node (ref "C16") (pin "1") (pinfunction "1_1") (pintype "passive"))
      (node (ref "C17") (pin "2") (pinfunction "2_2") (pintype "passive"))
      (node (ref "C2") (pin "1") (pinfunction "1_1") (pintype "passive"))
      (node (ref "C3") (pin "2") (pinfunction "2_2") (pintype "passive"))
      (node (ref "C4") (pin "2") (pinfunction "2_2") (pintype "passive"))
      (node (ref "C5") (pin "2") (pinfunction "2_2") (pintype "passive"))
      (node (ref "C6") (pin "2") (pinfunction "2_2") (pintype "passive"))
      (node (ref "C7") (pin "2") (pinfunction "2_2") (pintype "passive"))
      (node (ref "C8") (pin "2") (pinfunction "2_2") (pintype "passive"))
      (node (ref "C9") (pin "2") (pinfunction "2_2") (pintype "passive"))
      (node (ref "D1") (pin "1") (pinfunction "1_1") (pintype "passive"))
      (node (ref "D3") (pin "1") (pinfunction "1_1") (pintype "passive"))
      (node (ref "D4") (pin "1") (pinfunction "1_1") (pintype "passive"))
      (node (ref "D5") (pin "1") (pinfunction "1_1") (pintype "passive"))
      (node (ref "D6") (pin "1") (pinfunction "1_1") (pintype "passive"))
      (node (ref "D7") (pin "1") (pinfunction "1_1") (pintype "passive"))
      (node (ref "D8") (pin "1") (pinfunction "1_1") (pintype "passive"))
      (node (ref "J1") (pin "1") (pinfunction "1_1") (pintype "passive"))
      (node (ref "J1") (pin "23") (pinfunction "23_23") (pintype "passive"))
      (node (ref "J2") (pin "2") (pinfunction "2_2") (pintype "passive"))
      (node (ref "J2") (pin "24") (pinfunction "24_24") (pintype "passive"))
      (node (ref "J3") (pin "A1B12") (pinfunction "GND_A1B12_A1B12") (pintype "passive"))
      (node (ref "J3") (pin "B1A12") (pinfunction "GND_B1A12_B1A12") (pintype "passive"))
      (node (ref "J3") (pin "S1") (pinfunction "SHIELD_1_S1") (pintype "passive"))
      (node (ref "J3") (pin "S2") (pinfunction "SHIELD_2_S2") (pintype "passive"))
      (node (ref "J3") (pin "S3") (pinfunction "SHIELD_3_S3") (pintype "passive"))
      (node (ref "J3") (pin "S4") (pinfunction "SHIELD_4_S4") (pintype "passive"))
      (node (ref "J4") (pin "A1B12") (pinfunction "GND_A1B12_A1B12") (pintype "passive"))
      (node (ref "J4") (pin "B1A12") (pinfunction "GND_B1A12_B1A12") (pintype "passive"))
      (node (ref "J4") (pin "S1") (pinfunction "SHIELD_1_S1") (pintype "passive"))
      (node (ref "J4") (pin "S2") (pinfunction "SHIELD_2_S2") (pintype "passive"))
      (node (ref "J4") (pin "S3") (pinfunction "SHIELD_3_S3") (pintype "passive"))
      (node (ref "J4") (pin "S4") (pinfunction "SHIELD_4_S4") (pintype "passive"))
      (node (ref "R11") (pin "1") (pinfunction "1_1") (pintype "passive"))
      (node (ref "R12") (pin "1") (pinfunction "1_1") (pintype "passive"))
      (node (ref "R13") (pin "1") (pinfunction "1_1") (pintype "passive"))
      (node (ref "R14") (pin "1") (pinfunction "1_1") (pintype "passive"))
      (node (ref "R15") (pin "1") (pinfunction "1_1") (pintype "passive"))
      (node (ref "R9") (pin "2") (pinfunction "2_2") (pintype "passive"))
      (node (ref "SW1") (pin "3") (pinfunction "3_3") (pintype "passive"))
      (node (ref "SW1") (pin "4") (pinfunction "4_4") (pintype "passive"))
      (node (ref "SW2") (pin "3") (pinfunction "3_3") (pintype "passive"))
      (node (ref "SW2") (pin "4") (pinfunction "4_4") (pintype "passive"))
      (node (ref "U1") (pin "1") (pinfunction "GND_01_1") (pintype "passive"))
      (node (ref "U1") (pin "2") (pinfunction "GND_02_2") (pintype "passive"))
      (node (ref "U1") (pin "42") (pinfunction "GND_42") (pintype "passive"))
      (node (ref "U1") (pin "43") (pinfunction "GND_43") (pintype "passive"))
      (node (ref "U1") (pin "46") (pinfunction "GND_46_46") (pintype "passive"))
      (node (ref "U1") (pin "47") (pinfunction "GND_47_47") (pintype "passive"))
      (node (ref "U1") (pin "48") (pinfunction "GND_48_48") (pintype "passive"))
      (node (ref "U1") (pin "49") (pinfunction "GND_49_49") (pintype "passive"))
      (node (ref "U1") (pin "50") (pinfunction "GND_50_50") (pintype "passive"))
      (node (ref "U1") (pin "51") (pinfunction "GND_51_51") (pintype "passive"))
      (node (ref "U1") (pin "52") (pinfunction "GND_52_52") (pintype "passive"))
      (node (ref "U1") (pin "53") (pinfunction "GND_53_53") (pintype "passive"))
      (node (ref "U1") (pin "54") (pinfunction "GND_54_54") (pintype "passive"))
      (node (ref "U1") (pin "55") (pinfunction "GND_55_55") (pintype "passive"))
      (node (ref "U1") (pin "56") (pinfunction "GND_56_56") (pintype "passive"))
      (node (ref "U1") (pin "57") (pinfunction "GND_57_57") (pintype "passive"))
      (node (ref "U1") (pin "58") (pinfunction "GND_58_58") (pintype "passive"))
      (node (ref "U1") (pin "59") (pinfunction "GND_59_59") (pintype "passive"))
      (node (ref "U1") (pin "60") (pinfunction "GND_60_60") (pintype "passive"))
      (node (ref "U1") (pin "61") (pinfunction "GND_61_61") (pintype "passive"))
      (node (ref "U1") (pin "62") (pinfunction "GND_62_62") (pintype "passive"))
      (node (ref "U1") (pin "63") (pinfunction "GND_63_63") (pintype "passive"))
      (node (ref "U1") (pin "64") (pinfunction "GND_64_64") (pintype "passive"))
      (node (ref "U1") (pin "65") (pinfunction "GND_65_65") (pintype "passive"))
      (node (ref "U1") (pin "66") (pinfunction "GND_66_66") (pintype "passive"))
      (node (ref "U1") (pin "67") (pinfunction "GND_67_67") (pintype "passive"))
      (node (ref "U1") (pin "68") (pinfunction "GND_68_68") (pintype "passive"))
      (node (ref "U1") (pin "69") (pinfunction "GND_69_69") (pintype "passive"))
      (node (ref "U1") (pin "70") (pinfunction "GND_70_70") (pintype "passive"))
      (node (ref "U1") (pin "71") (pinfunction "GND_71_71") (pintype "passive"))
      (node (ref "U1") (pin "72") (pinfunction "GND_72_72") (pintype "passive"))
      (node (ref "U1") (pin "73") (pinfunction "GND_73_73") (pintype "passive"))
      (node (ref "U2") (pin "13") (pinfunction "GND_13") (pintype "passive"))
      (node (ref "U2") (pin "21") (pinfunction "GND_21") (pintype "passive"))
      (node (ref "U2") (pin "3") (pinfunction "GND_3") (pintype "passive"))
      (node (ref "U3") (pin "2") (pinfunction "GND_2") (pintype "power_in"))
      (node (ref "U3") (pin "4") (pinfunction "GND_4") (pintype "power_in"))
    )
    (net (code "65") (name "Net-(D1-Pad2)") (class "Default")
      (node (ref "D1") (pin "2") (pinfunction "2_2") (pintype "passive"))
      (node (ref "R3") (pin "1") (pinfunction "1_1") (pintype "passive"))
    )
    (net (code "66") (name "Net-(D2-Pad2)") (class "Default")
      (node (ref "D2") (pin "2") (pinfunction "2_2") (pintype "passive"))
      (node (ref "R4") (pin "1") (pinfunction "1_1") (pintype "passive"))
    )
    (net (code "67") (name "Net-(J3-CC1)") (class "Default")
      (node (ref "J3") (pin "A5") (pinfunction "CC1_A5") (pintype "passive"))
      (node (ref "R12") (pin "2") (pinfunction "2_2") (pintype "passive"))
    )
    (net (code "68") (name "Net-(J3-CC2)") (class "Default")
      (node (ref "J3") (pin "B5") (pinfunction "CC2_B5") (pintype "passive"))
      (node (ref "R11") (pin "2") (pinfunction "2_2") (pintype "passive"))
    )
    (net (code "69") (name "Net-(J4-CC1)") (class "Default")
      (node (ref "J4") (pin "A5") (pinfunction "CC1_A5") (pintype "passive"))
      (node (ref "R15") (pin "2") (pinfunction "2_2") (pintype "passive"))
    )
    (net (code "70") (name "Net-(J4-CC2)") (class "Default")
      (node (ref "J4") (pin "B5") (pinfunction "CC2_B5") (pintype "passive"))
      (node (ref "R14") (pin "2") (pinfunction "2_2") (pintype "passive"))
    )
    (net (code "71") (name "Net-(Q1-B)") (class "Default")
      (node (ref "Q1") (pin "1") (pinfunction "B_1") (pintype "passive"))
      (node (ref "R16") (pin "1") (pinfunction "1_1") (pintype "passive"))
    )
    (net (code "72") (name "Net-(Q2-B)") (class "Default")
      (node (ref "Q2") (pin "1") (pinfunction "B_1") (pintype "passive"))
      (node (ref "R18") (pin "1") (pinfunction "1_1") (pintype "passive"))
    )
    (net (code "73") (name "Net-(U2-CBUS0)") (class "Default")
      (node (ref "R9") (pin "1") (pinfunction "1_1") (pintype "passive"))
      (node (ref "U2") (pin "15") (pinfunction "CBUS0_15") (pintype "passive"))
    )
    (net (code "74") (name "unconnected-(J1-Pad24)") (class "Default")
      (node (ref "J1") (pin "24") (pinfunction "24_24") (pintype "passive+no_connect"))
    )
    (net (code "75") (name "unconnected-(J3-SBU1-PadA8)") (class "Default")
      (node (ref "J3") (pin "A8") (pinfunction "SBU1_A8") (pintype "passive+no_connect"))
    )
    (net (code "76") (name "unconnected-(J3-SBU2-PadB8)") (class "Default")
      (node (ref "J3") (pin "B8") (pinfunction "SBU2_B8") (pintype "passive+no_connect"))
    )
    (net (code "77") (name "unconnected-(J4-SBU1-PadA8)") (class "Default")
      (node (ref "J4") (pin "A8") (pinfunction "SBU1_A8") (pintype "passive+no_connect"))
    )
    (net (code "78") (name "unconnected-(J4-SBU2-PadB8)") (class "Default")
      (node (ref "J4") (pin "B8") (pinfunction "SBU2_B8") (pintype "passive+no_connect"))
    )
    (net (code "79") (name "unconnected-(U2-CBUS1-Pad14)") (class "Default")
      (node (ref "U2") (pin "14") (pinfunction "CBUS1_14") (pintype "passive+no_connect"))
    )
    (net (code "80") (name "unconnected-(U2-CBUS2-Pad7)") (class "Default")
      (node (ref "U2") (pin "7") (pinfunction "CBUS2_7") (pintype "passive+no_connect"))
    )
    (net (code "81") (name "unconnected-(U2-~{CTS}-Pad6)") (class "Default")
      (node (ref "U2") (pin "6") (pinfunction "~{CTS}_6") (pintype "passive+no_connect"))
    )
    (net (code "82") (name "unconnected-(U2-~{DCD}-Pad5)") (class "Default")
      (node (ref "U2") (pin "5") (pinfunction "~{DCD}_5") (pintype "passive+no_connect"))
    )
    (net (code "83") (name "unconnected-(U2-~{DSR}-Pad4)") (class "Default")
      (node (ref "U2") (pin "4") (pinfunction "~{DSR}_4") (pintype "passive+no_connect"))
    )
    (net (code "84") (name "unconnected-(U2-~{RI}-Pad2)") (class "Default")
      (node (ref "U2") (pin "2") (pinfunction "~{RI}_2") (pintype "passive+no_connect"))
    )
  )
)
